# Coffee_Roaster_V2_0_Final_2025_02_24_A.net
KiCad netlist of a schematic drawn in EAGLE
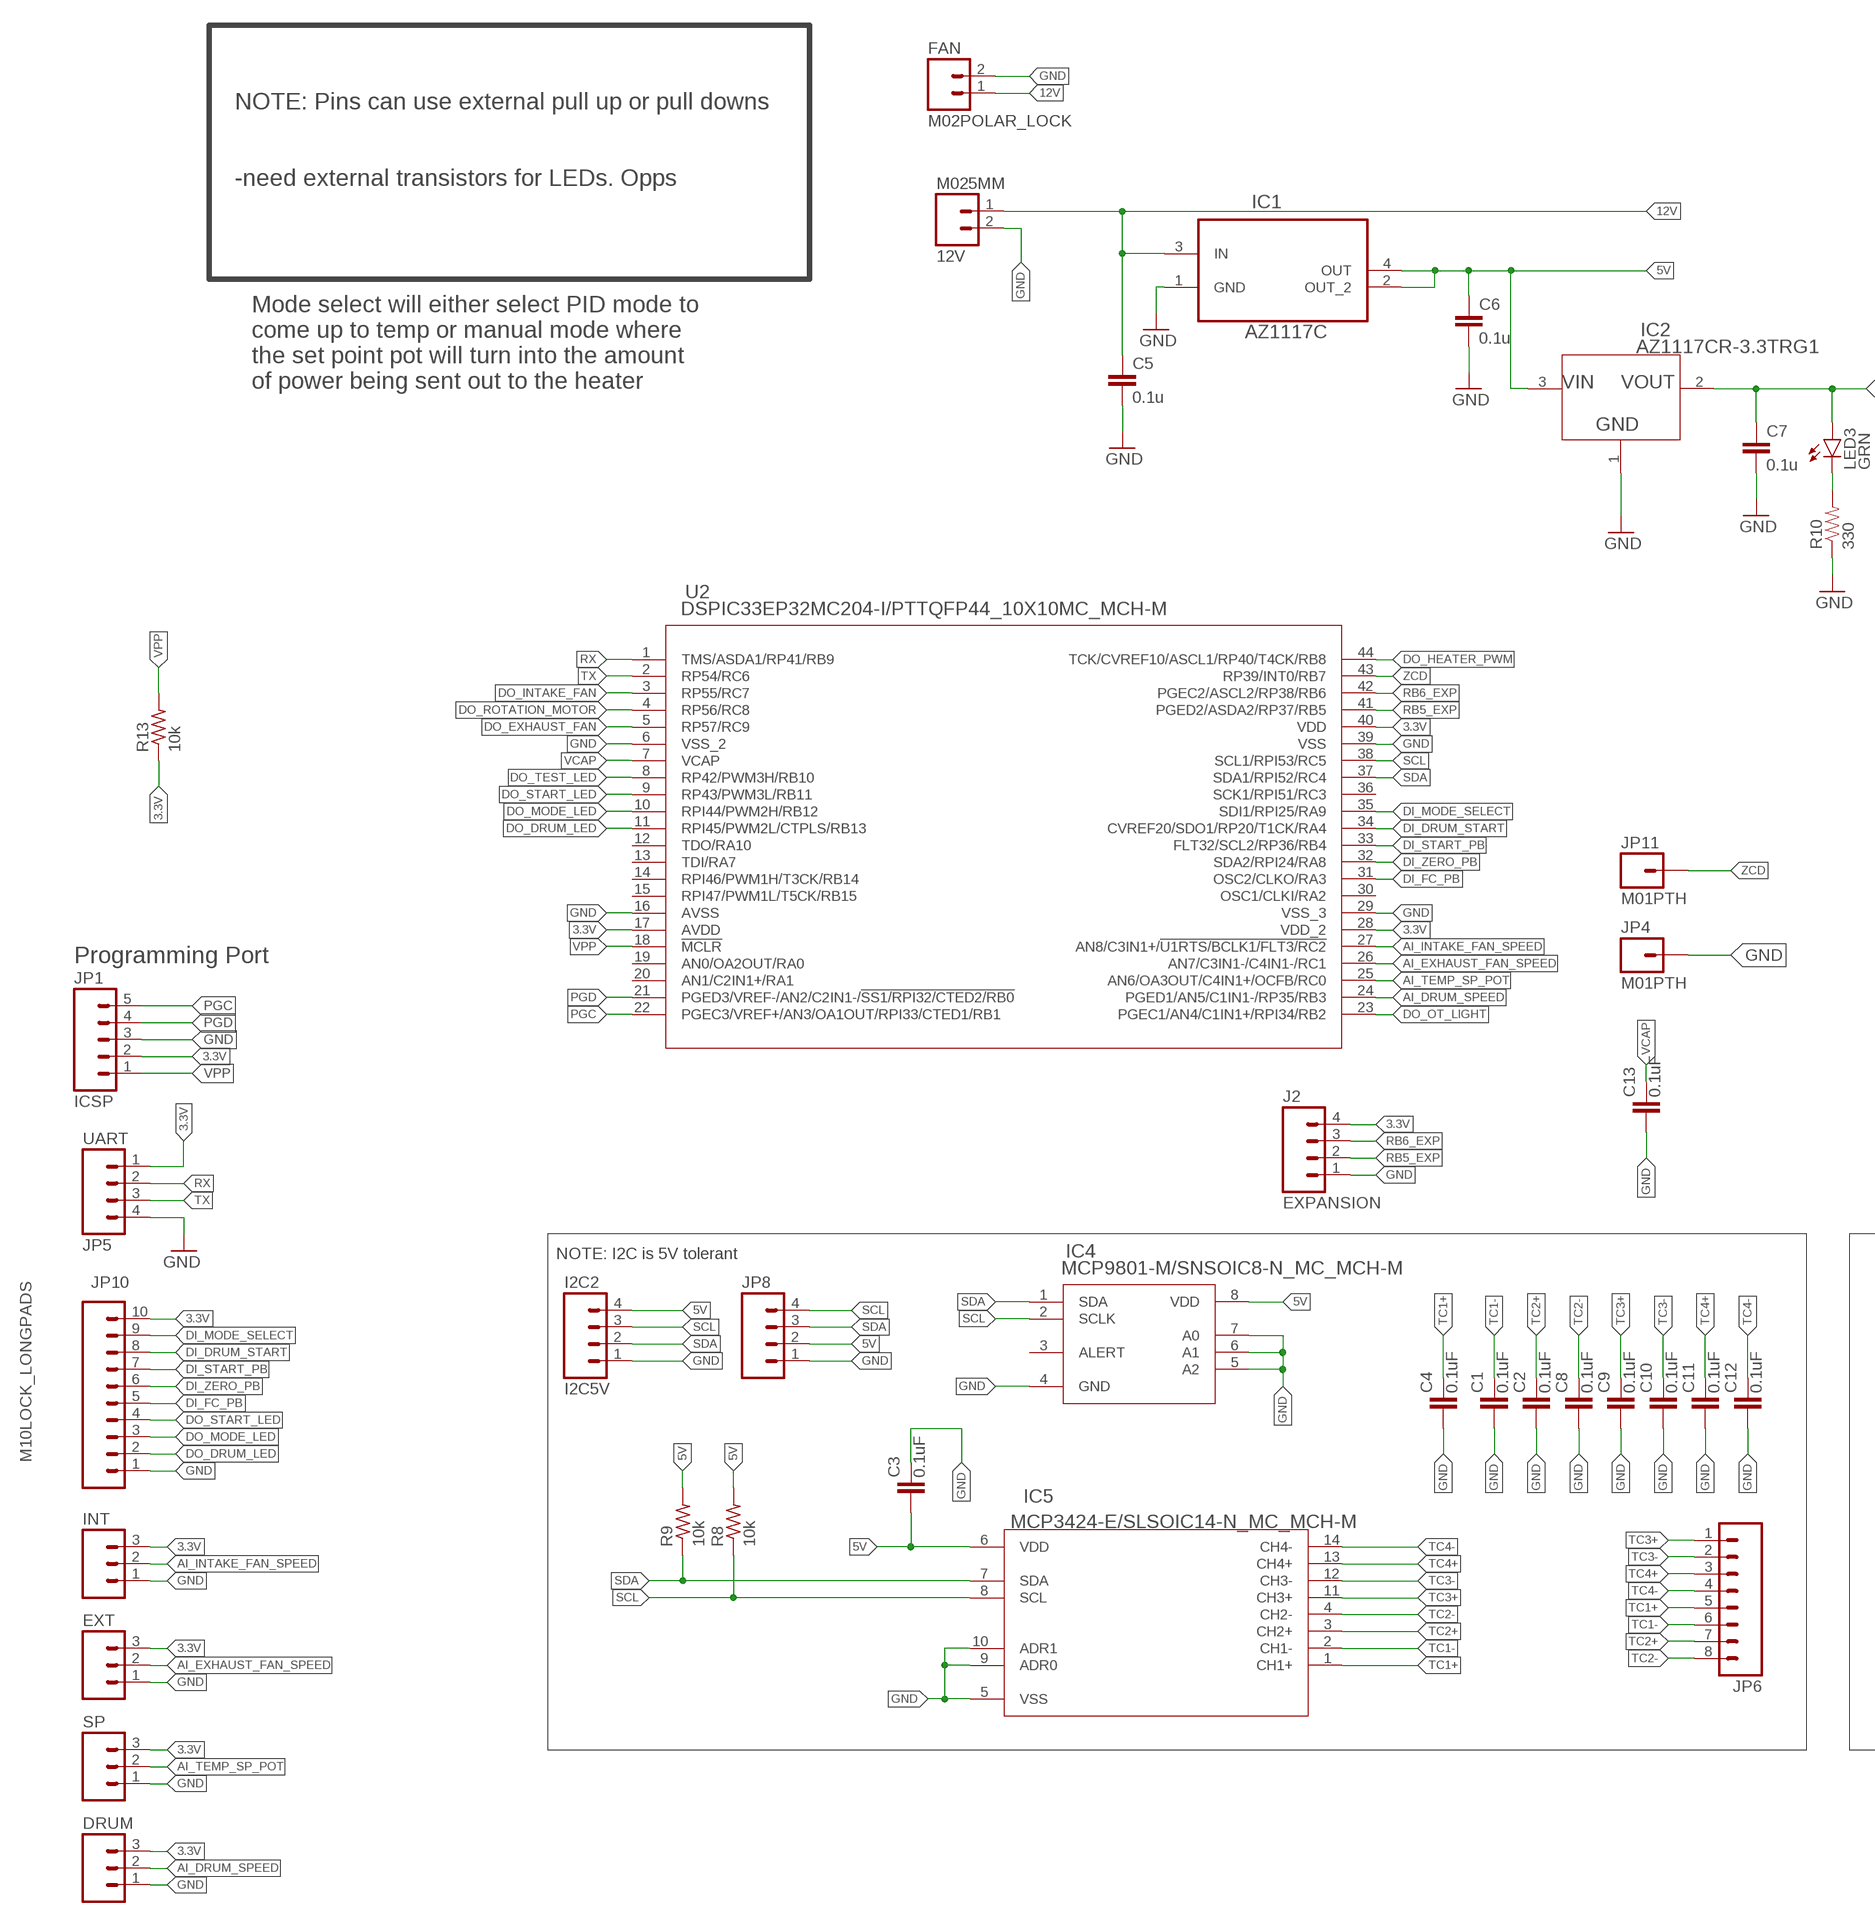
[diagram p0: schematic, sheet 1, part 1 of 2]
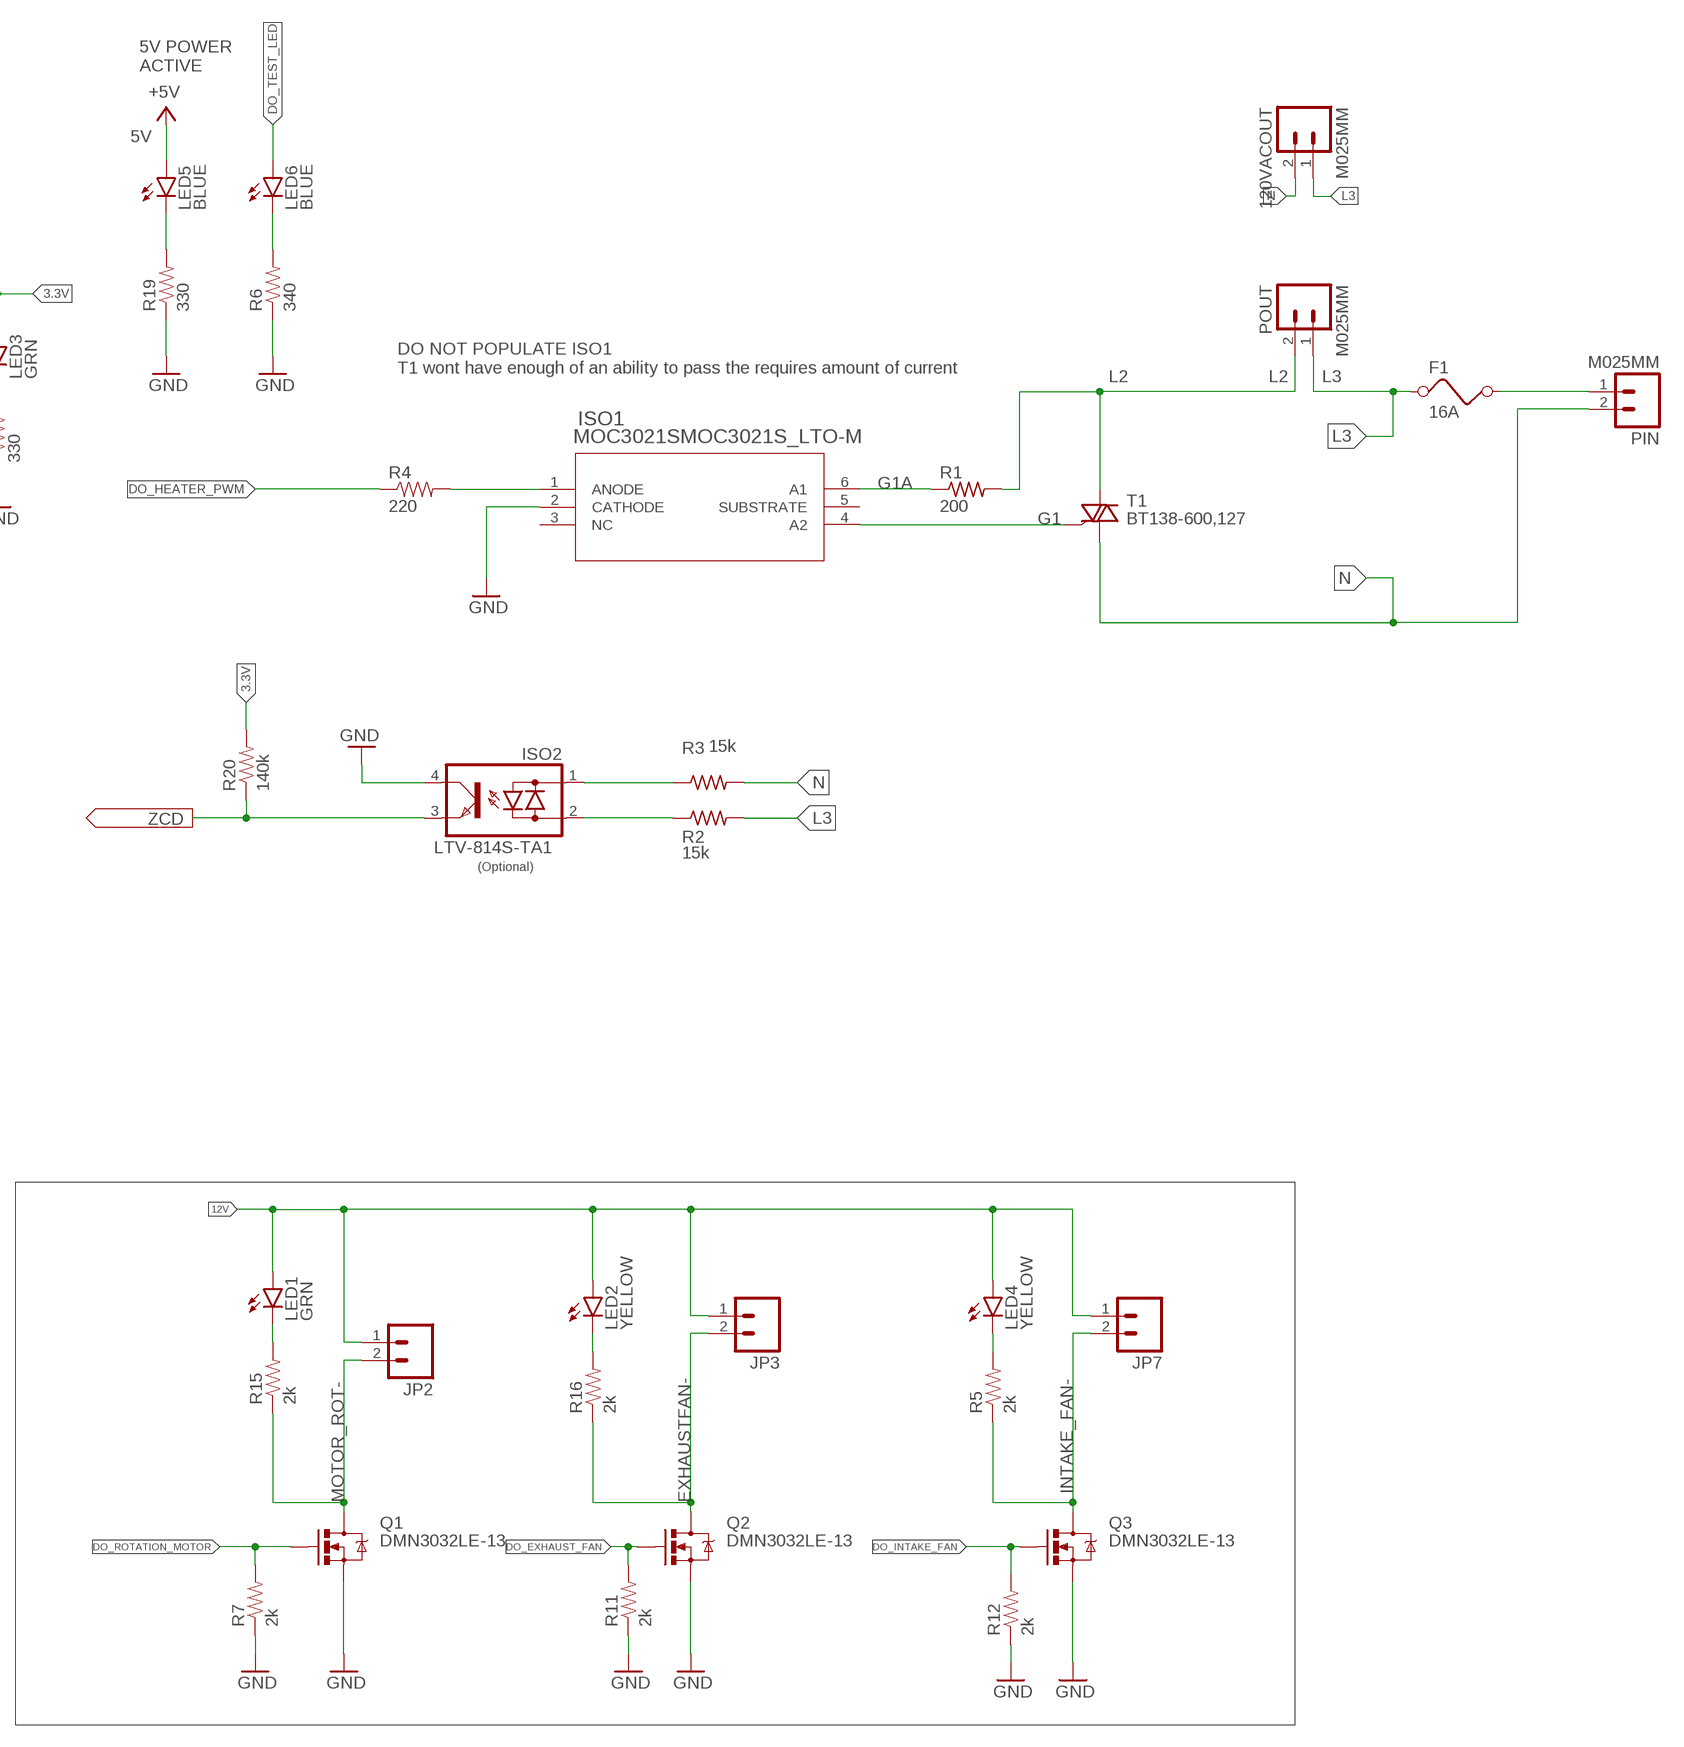
[diagram p1: schematic, sheet 1, part 2 of 2]

(export (version "E")
  (design (tool "Eeschema 10.0.6"))
  (components
    (comp (ref "12V")
      (value "M025MM")
      (footprint "eagle-import:SCREWTERMINAL-5MM-2")
      (libsource (lib "eagle-import") (part "SparkFun-Connectors_M025MM"))
    )
    (comp (ref "120VACOUT")
      (value "M025MM")
      (footprint "eagle-import:SCREWTERMINAL-5MM-2")
      (libsource (lib "eagle-import") (part "SparkFun-Connectors_M025MM"))
    )
    (comp (ref "C1")
      (value "0.1uF")
      (footprint "eagle-import:0805")
      (libsource (lib "eagle-import") (part "SparkFun-Capacitors_CAP0805"))
    )
    (comp (ref "C2")
      (value "0.1uF")
      (footprint "eagle-import:0805")
      (libsource (lib "eagle-import") (part "SparkFun-Capacitors_CAP0805"))
    )
    (comp (ref "C3")
      (value "0.1uF")
      (footprint "eagle-import:0805")
      (libsource (lib "eagle-import") (part "SparkFun-Capacitors_CAP0805"))
    )
    (comp (ref "C4")
      (value "0.1uF")
      (footprint "eagle-import:0805")
      (libsource (lib "eagle-import") (part "SparkFun-Capacitors_CAP0805"))
    )
    (comp (ref "C5")
      (value "0.1u")
      (footprint "eagle-import:1206")
      (libsource (lib "eagle-import") (part "CAP1206"))
    )
    (comp (ref "C6")
      (value "0.1u")
      (footprint "eagle-import:1206")
      (libsource (lib "eagle-import") (part "CAP1206"))
    )
    (comp (ref "C7")
      (value "0.1u")
      (footprint "eagle-import:1206")
      (libsource (lib "eagle-import") (part "CAP1206"))
    )
    (comp (ref "C8")
      (value "0.1uF")
      (footprint "eagle-import:0805")
      (libsource (lib "eagle-import") (part "SparkFun-Capacitors_CAP0805"))
    )
    (comp (ref "C9")
      (value "0.1uF")
      (footprint "eagle-import:0805")
      (libsource (lib "eagle-import") (part "SparkFun-Capacitors_CAP0805"))
    )
    (comp (ref "C10")
      (value "0.1uF")
      (footprint "eagle-import:0805")
      (libsource (lib "eagle-import") (part "SparkFun-Capacitors_CAP0805"))
    )
    (comp (ref "C11")
      (value "0.1uF")
      (footprint "eagle-import:0805")
      (libsource (lib "eagle-import") (part "SparkFun-Capacitors_CAP0805"))
    )
    (comp (ref "C12")
      (value "0.1uF")
      (footprint "eagle-import:0805")
      (libsource (lib "eagle-import") (part "SparkFun-Capacitors_CAP0805"))
    )
    (comp (ref "C13")
      (value "0.1uF")
      (footprint "eagle-import:0805")
      (libsource (lib "eagle-import") (part "SparkFun-Capacitors_CAP0805"))
    )
    (comp (ref "DRUM")
      (value "M03POLAR_LOCK")
      (footprint "eagle-import:MOLEX-1X3_LOCK")
      (libsource (lib "eagle-import") (part "M03POLAR_LOCK"))
    )
    (comp (ref "EXT")
      (value "M03POLAR_LOCK")
      (footprint "eagle-import:MOLEX-1X3_LOCK")
      (libsource (lib "eagle-import") (part "M03POLAR_LOCK"))
    )
    (comp (ref "F1")
      (value "16A")
      (footprint "eagle-import:FUSE")
      (libsource (lib "eagle-import") (part "FUSE"))
    )
    (comp (ref "FAN")
      (value "M02POLAR_LOCK")
      (footprint "eagle-import:MOLEX-1X2_LOCK")
      (libsource (lib "eagle-import") (part "SparkFun-Connectors_M02POLAR_LOCK"))
    )
    (comp (ref "I2C2")
      (value "I2C5V")
      (footprint "eagle-import:1X04-1.5MM_JST")
      (libsource (lib "eagle-import") (part "M04JST"))
    )
    (comp (ref "IC1")
      (value "AZ1117C")
      (footprint "eagle-import:SOT230P700X180-4N")
      (fields (field (name "MPN") "ADP3338AKCZ-5-R7"))
      (libsource (lib "eagle-import") (part "ADP3338AKCZ-5-R7"))
    )
    (comp (ref "IC2")
      (value "AZ1117CR-3.3TRG1")
      (footprint "eagle-import:SOT89_AZ1117_DIO")
      (fields (field (name "COPYRIGHT") "Copyright (C) 2022 Ultra Librarian. All rights reserved."))
      (libsource (lib "eagle-import") (part "AZ1117CR-3.3TRG1"))
    )
    (comp (ref "IC4")
      (value "MCP9801-M/SNSOIC8-N_MC_MCH-M")
      (footprint "eagle-import:SOIC8-N_MC_MCH-M")
      (fields
        (field (name "MANUFACTURER_PART_NUMBER") "MCP9801-M/SN")
        (field (name "COPYRIGHT") "Copyright (C) 2023 Ultra Librarian. All rights reserved.")
      )
      (libsource (lib "eagle-import") (part "MCP9801-M/SNSOIC8-N_MC_MCH-M"))
    )
    (comp (ref "IC5")
      (value "MCP3424-E/SLSOIC14-N_MC_MCH-M")
      (footprint "eagle-import:SOIC14-N_MC_MCH-M")
      (fields
        (field (name "MANUFACTURER_PART_NUMBER") "MCP3424-E/SL")
        (field (name "COPYRIGHT") "Copyright (C) 2023 Ultra Librarian. All rights reserved.")
      )
      (libsource (lib "eagle-import") (part "MCP3424-E/SLSOIC14-N_MC_MCH-M"))
    )
    (comp (ref "INT")
      (value "M03POLAR_LOCK")
      (footprint "eagle-import:MOLEX-1X3_LOCK")
      (libsource (lib "eagle-import") (part "M03POLAR_LOCK"))
    )
    (comp (ref "ISO1")
      (value "MOC3021SMOC3021S_LTO-M")
      (footprint "eagle-import:MOC3021S_LTO-M")
      (fields
        (field (name "MANUFACTURER_PART_NUMBER") "MOC3021S")
        (field (name "COPYRIGHT") "Copyright (C) 2018 Accelerated Designs. All rights reserved")
      )
      (libsource (lib "eagle-import") (part "MOC3021SMOC3021S_LTO-M"))
    )
    (comp (ref "ISO2")
      (value "LTV-814S-TA1")
      (footprint "eagle-import:DIL4-SMD")
      (fields (field (name "MF") "VISHAY/TELEFUNKEN") (field (name "MPN") "SFH6206-3"))
      (libsource (lib "eagle-import") (part "SFH6206"))
    )
    (comp (ref "J2")
      (value "EXPANSION")
      (footprint "eagle-import:1X04-1.5MM_JST")
      (libsource (lib "eagle-import") (part "M04JST"))
    )
    (comp (ref "JP1")
      (value "ICSP")
      (footprint "eagle-import:1X05")
      (libsource (lib "eagle-import") (part "M05PTH"))
    )
    (comp (ref "JP2")
      (value "M02POLAR_LOCK")
      (footprint "eagle-import:MOLEX-1X2_LOCK")
      (libsource (lib "eagle-import") (part "M02POLAR_LOCK"))
    )
    (comp (ref "JP3")
      (value "M02POLAR_LOCK")
      (footprint "eagle-import:MOLEX-1X2_LOCK")
      (libsource (lib "eagle-import") (part "M02POLAR_LOCK"))
    )
    (comp (ref "JP4")
      (value "M01PTH")
      (footprint "eagle-import:1X01")
      (libsource (lib "eagle-import") (part "M01PTH"))
    )
    (comp (ref "JP5")
      (value "UART")
      (footprint "eagle-import:1X04_LOCK")
      (libsource (lib "eagle-import") (part "M04LOCK"))
    )
    (comp (ref "JP6")
      (value "M083.5MM-8")
      (footprint "eagle-import:SCREWTERMINAL-3.5MM-8")
      (libsource (lib "eagle-import") (part "M083.5MM-8"))
    )
    (comp (ref "JP7")
      (value "M02POLAR_LOCK")
      (footprint "eagle-import:MOLEX-1X2_LOCK")
      (libsource (lib "eagle-import") (part "M02POLAR_LOCK"))
    )
    (comp (ref "JP8")
      (value "M04LOCK_LONGPADS")
      (footprint "eagle-import:1X04_LOCK_LONGPADS")
      (libsource (lib "eagle-import") (part "M04LOCK_LONGPADS"))
    )
    (comp (ref "JP10")
      (value "M10LOCK_LONGPADS")
      (footprint "eagle-import:1X10_LOCK_LONGPADS")
      (libsource (lib "eagle-import") (part "M10LOCK_LONGPADS"))
    )
    (comp (ref "JP11")
      (value "M01PTH")
      (footprint "eagle-import:1X01")
      (libsource (lib "eagle-import") (part "M01PTH"))
    )
    (comp (ref "LED1")
      (value "GRN")
      (footprint "eagle-import:LED-1206")
      (libsource (lib "eagle-import") (part "LED1206"))
    )
    (comp (ref "LED2")
      (value "YELLOW")
      (footprint "eagle-import:LED-1206")
      (libsource (lib "eagle-import") (part "LED1206"))
    )
    (comp (ref "LED3")
      (value "GRN")
      (footprint "eagle-import:LED-1206")
      (libsource (lib "eagle-import") (part "LED1206"))
    )
    (comp (ref "LED4")
      (value "YELLOW")
      (footprint "eagle-import:LED-1206")
      (libsource (lib "eagle-import") (part "LED1206"))
    )
    (comp (ref "LED5")
      (value "BLUE")
      (footprint "eagle-import:LED-1206")
      (libsource (lib "eagle-import") (part "LED1206"))
    )
    (comp (ref "LED6")
      (value "BLUE")
      (footprint "eagle-import:LED-1206")
      (libsource (lib "eagle-import") (part "LED1206"))
    )
    (comp (ref "PIN")
      (value "M025MM")
      (footprint "eagle-import:SCREWTERMINAL-5MM-2")
      (libsource (lib "eagle-import") (part "SparkFun-Connectors_M025MM"))
    )
    (comp (ref "POUT")
      (value "M025MM")
      (footprint "eagle-import:SCREWTERMINAL-5MM-2")
      (libsource (lib "eagle-import") (part "SparkFun-Connectors_M025MM"))
    )
    (comp (ref "Q1")
      (value "DMN3032LE-13")
      (footprint "eagle-import:SOT223")
      (libsource (lib "eagle-import") (part "NFET_SOT_223"))
    )
    (comp (ref "Q2")
      (value "DMN3032LE-13")
      (footprint "eagle-import:SOT223")
      (libsource (lib "eagle-import") (part "NFET_SOT_223"))
    )
    (comp (ref "Q3")
      (value "DMN3032LE-13")
      (footprint "eagle-import:SOT223")
      (libsource (lib "eagle-import") (part "NFET_SOT_223"))
    )
    (comp (ref "R1")
      (value "200")
      (footprint "eagle-import:R2512")
      (libsource (lib "eagle-import") (part "rcl_334_R-US_R2512"))
    )
    (comp (ref "R2")
      (value "15k")
      (footprint "eagle-import:R2512")
      (libsource (lib "eagle-import") (part "rcl_334_R-US_R2512"))
    )
    (comp (ref "R3")
      (value "15k")
      (footprint "eagle-import:R2512")
      (libsource (lib "eagle-import") (part "rcl_334_R-US_R2512"))
    )
    (comp (ref "R4")
      (value "220")
      (footprint "eagle-import:1206")
      (libsource (lib "eagle-import") (part "RESISTOR1206"))
    )
    (comp (ref "R5")
      (value "2k")
      (footprint "eagle-import:1206")
      (libsource (lib "eagle-import") (part "RESISTOR1206"))
    )
    (comp (ref "R6")
      (value "340")
      (footprint "eagle-import:1206")
      (libsource (lib "eagle-import") (part "RESISTOR1206"))
    )
    (comp (ref "R7")
      (value "2k")
      (footprint "eagle-import:1206")
      (libsource (lib "eagle-import") (part "RESISTOR1206"))
    )
    (comp (ref "R8")
      (value "10k")
      (footprint "eagle-import:M0805")
      (libsource (lib "eagle-import") (part "R-US_M0805"))
    )
    (comp (ref "R9")
      (value "10k")
      (footprint "eagle-import:M0805")
      (libsource (lib "eagle-import") (part "R-US_M0805"))
    )
    (comp (ref "R10")
      (value "330")
      (footprint "eagle-import:1206")
      (libsource (lib "eagle-import") (part "RESISTOR1206"))
    )
    (comp (ref "R11")
      (value "2k")
      (footprint "eagle-import:1206")
      (libsource (lib "eagle-import") (part "RESISTOR1206"))
    )
    (comp (ref "R12")
      (value "2k")
      (footprint "eagle-import:1206")
      (libsource (lib "eagle-import") (part "RESISTOR1206"))
    )
    (comp (ref "R13")
      (value "10k")
      (footprint "eagle-import:M0805")
      (libsource (lib "eagle-import") (part "R-US_M0805"))
    )
    (comp (ref "R15")
      (value "2k")
      (footprint "eagle-import:1206")
      (libsource (lib "eagle-import") (part "RESISTOR1206"))
    )
    (comp (ref "R16")
      (value "2k")
      (footprint "eagle-import:1206")
      (libsource (lib "eagle-import") (part "RESISTOR1206"))
    )
    (comp (ref "R19")
      (value "330")
      (footprint "eagle-import:1206")
      (libsource (lib "eagle-import") (part "RESISTOR1206"))
    )
    (comp (ref "R20")
      (value "140k")
      (footprint "eagle-import:1206")
      (libsource (lib "eagle-import") (part "RESISTOR1206"))
    )
    (comp (ref "SP")
      (value "M03POLAR_LOCK")
      (footprint "eagle-import:MOLEX-1X3_LOCK")
      (libsource (lib "eagle-import") (part "M03POLAR_LOCK"))
    )
    (comp (ref "T1")
      (value "BT138-600,127")
      (footprint "eagle-import:TO220BV")
      (libsource (lib "eagle-import") (part "BT138-V"))
    )
    (comp (ref "U2")
      (value "DSPIC33EP32MC204-I/PTTQFP44_10X10MC_MCH-M")
      (footprint "eagle-import:TQFP44_10X10MC_MCH-M")
      (fields
        (field (name "MANUFACTURER_PART_NUMBER") "DSPIC33EP32MC204-I/PT")
        (field (name "COPYRIGHT") "Copyright (C) 2021 Ultra Librarian. All rights reserved.")
      )
      (libsource (lib "eagle-import") (part "DSPIC33EP32MC204-I/PTTQFP44_10X10MC_MCH-M"))
    )
  )
  (nets
    (net (code "1") (name "3.3V") (class "Default")
      (node (ref "C7") (pin "1") (pinfunction "1_1") (pintype "passive"))
      (node (ref "DRUM") (pin "3") (pinfunction "3_3") (pintype "passive"))
      (node (ref "EXT") (pin "3") (pinfunction "3_3") (pintype "passive"))
      (node (ref "IC2") (pin "2") (pinfunction "OUTPUT_2") (pintype "output"))
      (node (ref "INT") (pin "3") (pinfunction "3_3") (pintype "passive"))
      (node (ref "J2") (pin "4") (pinfunction "4_4") (pintype "passive"))
      (node (ref "JP1") (pin "2") (pinfunction "2_2") (pintype "passive"))
      (node (ref "JP10") (pin "10") (pinfunction "10_10") (pintype "passive"))
      (node (ref "JP5") (pin "1") (pinfunction "1_1") (pintype "passive"))
      (node (ref "LED3") (pin "A") (pinfunction "A_A") (pintype "passive"))
      (node (ref "R13") (pin "1") (pinfunction "1_1") (pintype "passive"))
      (node (ref "R20") (pin "2") (pinfunction "2_2") (pintype "passive"))
      (node (ref "SP") (pin "3") (pinfunction "3_3") (pintype "passive"))
      (node (ref "U2") (pin "17") (pinfunction "AVDD_17") (pintype "power_in"))
      (node (ref "U2") (pin "28") (pinfunction "VDD_2_28") (pintype "power_in"))
      (node (ref "U2") (pin "40") (pinfunction "VDD_40") (pintype "power_in"))
    )
    (net (code "2") (name "5V") (class "Default")
      (node (ref "C3") (pin "1") (pinfunction "1_1") (pintype "passive"))
      (node (ref "C6") (pin "1") (pinfunction "1_1") (pintype "passive"))
      (node (ref "I2C2") (pin "4") (pinfunction "4_4") (pintype "passive"))
      (node (ref "IC1") (pin "2") (pinfunction "OUT_2_2") (pintype "output"))
      (node (ref "IC1") (pin "4") (pinfunction "OUT_4") (pintype "output"))
      (node (ref "IC2") (pin "3") (pinfunction "INPUT_3") (pintype "input"))
      (node (ref "IC4") (pin "8") (pinfunction "VDD_8") (pintype "passive"))
      (node (ref "IC5") (pin "6") (pinfunction "VDD_6") (pintype "power_in"))
      (node (ref "JP8") (pin "2") (pinfunction "2_2") (pintype "passive"))
      (node (ref "LED5") (pin "A") (pinfunction "A_A") (pintype "passive"))
      (node (ref "R8") (pin "2") (pinfunction "2_2") (pintype "passive"))
      (node (ref "R9") (pin "2") (pinfunction "2_2") (pintype "passive"))
    )
    (net (code "3") (name "12V") (class "Default")
      (node (ref "12V") (pin "1") (pinfunction "1_1") (pintype "passive"))
      (node (ref "C5") (pin "1") (pinfunction "1_1") (pintype "passive"))
      (node (ref "FAN") (pin "1") (pinfunction "1_1") (pintype "passive"))
      (node (ref "IC1") (pin "3") (pinfunction "IN_3") (pintype "input"))
      (node (ref "JP2") (pin "1") (pinfunction "1_1") (pintype "passive"))
      (node (ref "JP3") (pin "1") (pinfunction "1_1") (pintype "passive"))
      (node (ref "JP7") (pin "1") (pinfunction "1_1") (pintype "passive"))
      (node (ref "LED1") (pin "A") (pinfunction "A_A") (pintype "passive"))
      (node (ref "LED2") (pin "A") (pinfunction "A_A") (pintype "passive"))
      (node (ref "LED4") (pin "A") (pinfunction "A_A") (pintype "passive"))
    )
    (net (code "4") (name "AI_DRUM_SPEED") (class "Default")
      (node (ref "DRUM") (pin "2") (pinfunction "2_2") (pintype "passive"))
      (node (ref "U2") (pin "24") (pinfunction "PGED1/AN5/C1IN1-/RP35/RB3_24") (pintype "bidirectional"))
    )
    (net (code "5") (name "AI_EXHAUST_FAN_SPEED") (class "Default")
      (node (ref "EXT") (pin "2") (pinfunction "2_2") (pintype "passive"))
      (node (ref "U2") (pin "26") (pinfunction "AN7/C3IN1-/C4IN1-/RC1_26") (pintype "bidirectional"))
    )
    (net (code "6") (name "AI_INTAKE_FAN_SPEED") (class "Default")
      (node (ref "INT") (pin "2") (pinfunction "2_2") (pintype "passive"))
      (node (ref "U2") (pin "27") (pinfunction "AN8/C3IN1+/~{U1RTS/BCLK1/FLT3/RC2}_27") (pintype "bidirectional"))
    )
    (net (code "7") (name "AI_TEMP_SP_POT") (class "Default")
      (node (ref "SP") (pin "2") (pinfunction "2_2") (pintype "passive"))
      (node (ref "U2") (pin "25") (pinfunction "AN6/OA3OUT/C4IN1+/OCFB/RC0_25") (pintype "bidirectional"))
    )
    (net (code "8") (name "DI_DRUM_START") (class "Default")
      (node (ref "JP10") (pin "8") (pinfunction "8_8") (pintype "passive"))
      (node (ref "U2") (pin "34") (pinfunction "CVREF20/SDO1/RP20/T1CK/RA4_34") (pintype "bidirectional"))
    )
    (net (code "9") (name "DI_FC_PB") (class "Default")
      (node (ref "JP10") (pin "5") (pinfunction "5_5") (pintype "passive"))
      (node (ref "U2") (pin "31") (pinfunction "OSC2/CLKO/RA3_31") (pintype "bidirectional"))
    )
    (net (code "10") (name "DI_MODE_SELECT") (class "Default")
      (node (ref "JP10") (pin "9") (pinfunction "9_9") (pintype "passive"))
      (node (ref "U2") (pin "35") (pinfunction "SDI1/RPI25/RA9_35") (pintype "bidirectional"))
    )
    (net (code "11") (name "DI_START_PB") (class "Default")
      (node (ref "JP10") (pin "7") (pinfunction "7_7") (pintype "passive"))
      (node (ref "U2") (pin "33") (pinfunction "FLT32/SCL2/RP36/RB4_33") (pintype "bidirectional"))
    )
    (net (code "12") (name "DI_ZERO_PB") (class "Default")
      (node (ref "JP10") (pin "6") (pinfunction "6_6") (pintype "passive"))
      (node (ref "U2") (pin "32") (pinfunction "SDA2/RPI24/RA8_32") (pintype "bidirectional"))
    )
    (net (code "13") (name "DO_DRUM_LED") (class "Default")
      (node (ref "JP10") (pin "2") (pinfunction "2_2") (pintype "passive"))
      (node (ref "U2") (pin "11") (pinfunction "RPI45/PWM2L/CTPLS/RB13_11") (pintype "bidirectional"))
    )
    (net (code "14") (name "DO_EXHAUST_FAN") (class "Default")
      (node (ref "Q2") (pin "1") (pinfunction "G_1") (pintype "passive"))
      (node (ref "R11") (pin "2") (pinfunction "2_2") (pintype "passive"))
      (node (ref "U2") (pin "5") (pinfunction "RP57/RC9_5") (pintype "bidirectional"))
    )
    (net (code "15") (name "DO_HEATER_PWM") (class "Default")
      (node (ref "R4") (pin "1") (pinfunction "1_1") (pintype "passive"))
      (node (ref "U2") (pin "44") (pinfunction "TCK/CVREF10/ASCL1/RP40/T4CK/RB8_44") (pintype "bidirectional"))
    )
    (net (code "16") (name "DO_INTAKE_FAN") (class "Default")
      (node (ref "Q3") (pin "1") (pinfunction "G_1") (pintype "passive"))
      (node (ref "R12") (pin "2") (pinfunction "2_2") (pintype "passive"))
      (node (ref "U2") (pin "3") (pinfunction "RP55/RC7_3") (pintype "bidirectional"))
    )
    (net (code "17") (name "DO_MODE_LED") (class "Default")
      (node (ref "JP10") (pin "3") (pinfunction "3_3") (pintype "passive"))
      (node (ref "U2") (pin "10") (pinfunction "RPI44/PWM2H/RB12_10") (pintype "bidirectional"))
    )
    (net (code "18") (name "DO_OT_LIGHT") (class "Default")
      (node (ref "U2") (pin "23") (pinfunction "PGEC1/AN4/C1IN1+/RPI34/RB2_23") (pintype "bidirectional"))
    )
    (net (code "19") (name "DO_ROTATION_MOTOR") (class "Default")
      (node (ref "Q1") (pin "1") (pinfunction "G_1") (pintype "passive"))
      (node (ref "R7") (pin "2") (pinfunction "2_2") (pintype "passive"))
      (node (ref "U2") (pin "4") (pinfunction "RP56/RC8_4") (pintype "bidirectional"))
    )
    (net (code "20") (name "DO_START_LED") (class "Default")
      (node (ref "JP10") (pin "4") (pinfunction "4_4") (pintype "passive"))
      (node (ref "U2") (pin "9") (pinfunction "RP43/PWM3L/RB11_9") (pintype "bidirectional"))
    )
    (net (code "21") (name "DO_TEST_LED") (class "Default")
      (node (ref "LED6") (pin "A") (pinfunction "A_A") (pintype "passive"))
      (node (ref "U2") (pin "8") (pinfunction "RP42/PWM3H/RB10_8") (pintype "bidirectional"))
    )
    (net (code "22") (name "EXHAUSTFAN-") (class "Default")
      (node (ref "JP3") (pin "2") (pinfunction "2_2") (pintype "passive"))
      (node (ref "Q2") (pin "2") (pinfunction "D_2") (pintype "passive"))
      (node (ref "Q2") (pin "4") (pinfunction "D_4") (pintype "passive"))
      (node (ref "R16") (pin "1") (pinfunction "1_1") (pintype "passive"))
    )
    (net (code "23") (name "G1") (class "Default")
      (node (ref "ISO1") (pin "4") (pinfunction "A2_4") (pintype "passive"))
      (node (ref "T1") (pin "G") (pinfunction "G_G") (pintype "passive"))
    )
    (net (code "24") (name "G1A") (class "Default")
      (node (ref "ISO1") (pin "6") (pinfunction "A1_6") (pintype "passive"))
      (node (ref "R1") (pin "1") (pinfunction "1_1") (pintype "passive"))
    )
    (net (code "25") (name "GND") (class "Default")
      (node (ref "12V") (pin "2") (pinfunction "2_2") (pintype "passive"))
      (node (ref "C1") (pin "1") (pinfunction "1_1") (pintype "passive"))
      (node (ref "C10") (pin "1") (pinfunction "1_1") (pintype "passive"))
      (node (ref "C11") (pin "1") (pinfunction "1_1") (pintype "passive"))
      (node (ref "C12") (pin "1") (pinfunction "1_1") (pintype "passive"))
      (node (ref "C13") (pin "1") (pinfunction "1_1") (pintype "passive"))
      (node (ref "C2") (pin "1") (pinfunction "1_1") (pintype "passive"))
      (node (ref "C3") (pin "2") (pinfunction "2_2") (pintype "passive"))
      (node (ref "C4") (pin "1") (pinfunction "1_1") (pintype "passive"))
      (node (ref "C5") (pin "2") (pinfunction "2_2") (pintype "passive"))
      (node (ref "C6") (pin "2") (pinfunction "2_2") (pintype "passive"))
      (node (ref "C7") (pin "2") (pinfunction "2_2") (pintype "passive"))
      (node (ref "C8") (pin "1") (pinfunction "1_1") (pintype "passive"))
      (node (ref "C9") (pin "1") (pinfunction "1_1") (pintype "passive"))
      (node (ref "DRUM") (pin "1") (pinfunction "1_1") (pintype "passive"))
      (node (ref "EXT") (pin "1") (pinfunction "1_1") (pintype "passive"))
      (node (ref "FAN") (pin "2") (pinfunction "2_2") (pintype "passive"))
      (node (ref "I2C2") (pin "1") (pinfunction "1_1") (pintype "passive"))
      (node (ref "IC1") (pin "1") (pinfunction "GND_1") (pintype "passive"))
      (node (ref "IC2") (pin "1") (pinfunction "ADJ/GND_1") (pintype "passive"))
      (node (ref "IC4") (pin "4") (pinfunction "GND_4") (pintype "passive"))
      (node (ref "IC4") (pin "5") (pinfunction "A2_5") (pintype "passive"))
      (node (ref "IC4") (pin "6") (pinfunction "A1_6") (pintype "passive"))
      (node (ref "IC4") (pin "7") (pinfunction "A0_7") (pintype "passive"))
      (node (ref "IC5") (pin "10") (pinfunction "ADR1_10") (pintype "passive"))
      (node (ref "IC5") (pin "5") (pinfunction "VSS_5") (pintype "power_in"))
      (node (ref "IC5") (pin "9") (pinfunction "ADR0_9") (pintype "passive"))
      (node (ref "INT") (pin "1") (pinfunction "1_1") (pintype "passive"))
      (node (ref "ISO1") (pin "2") (pinfunction "CATHODE_2") (pintype "passive"))
      (node (ref "ISO2") (pin "4") (pinfunction "C_4") (pintype "passive"))
      (node (ref "J2") (pin "1") (pinfunction "1_1") (pintype "passive"))
      (node (ref "JP1") (pin "3") (pinfunction "3_3") (pintype "passive"))
      (node (ref "JP10") (pin "1") (pinfunction "1_1") (pintype "passive"))
      (node (ref "JP4") (pin "1") (pinfunction "1_1") (pintype "passive"))
      (node (ref "JP5") (pin "4") (pinfunction "4_4") (pintype "passive"))
      (node (ref "JP8") (pin "1") (pinfunction "1_1") (pintype "passive"))
      (node (ref "Q1") (pin "3") (pinfunction "S_3") (pintype "passive"))
      (node (ref "Q2") (pin "3") (pinfunction "S_3") (pintype "passive"))
      (node (ref "Q3") (pin "3") (pinfunction "S_3") (pintype "passive"))
      (node (ref "R10") (pin "1") (pinfunction "1_1") (pintype "passive"))
      (node (ref "R11") (pin "1") (pinfunction "1_1") (pintype "passive"))
      (node (ref "R12") (pin "1") (pinfunction "1_1") (pintype "passive"))
      (node (ref "R19") (pin "1") (pinfunction "1_1") (pintype "passive"))
      (node (ref "R6") (pin "1") (pinfunction "1_1") (pintype "passive"))
      (node (ref "R7") (pin "1") (pinfunction "1_1") (pintype "passive"))
      (node (ref "SP") (pin "1") (pinfunction "1_1") (pintype "passive"))
      (node (ref "U2") (pin "16") (pinfunction "AVSS_16") (pintype "power_in"))
      (node (ref "U2") (pin "29") (pinfunction "VSS_3_29") (pintype "power_in"))
      (node (ref "U2") (pin "39") (pinfunction "VSS_39") (pintype "power_in"))
      (node (ref "U2") (pin "6") (pinfunction "VSS_2_6") (pintype "power_in"))
    )
    (net (code "26") (name "INTAKE_FAN-") (class "Default")
      (node (ref "JP7") (pin "2") (pinfunction "2_2") (pintype "passive"))
      (node (ref "Q3") (pin "2") (pinfunction "D_2") (pintype "passive"))
      (node (ref "Q3") (pin "4") (pinfunction "D_4") (pintype "passive"))
      (node (ref "R5") (pin "1") (pinfunction "1_1") (pintype "passive"))
    )
    (net (code "27") (name "L2") (class "Default")
      (node (ref "POUT") (pin "2") (pinfunction "2_2") (pintype "passive"))
      (node (ref "R1") (pin "2") (pinfunction "2_2") (pintype "passive"))
      (node (ref "T1") (pin "T2") (pinfunction "A2_T2") (pintype "passive"))
    )
    (net (code "28") (name "L3") (class "Default")
      (node (ref "120VACOUT") (pin "1") (pinfunction "1_1") (pintype "passive"))
      (node (ref "F1") (pin "1") (pinfunction "1_1") (pintype "passive"))
      (node (ref "POUT") (pin "1") (pinfunction "1_1") (pintype "passive"))
      (node (ref "R2") (pin "2") (pinfunction "2_2") (pintype "passive"))
    )
    (net (code "29") (name "MOTOR_ROT-") (class "Default")
      (node (ref "JP2") (pin "2") (pinfunction "2_2") (pintype "passive"))
      (node (ref "Q1") (pin "2") (pinfunction "D_2") (pintype "passive"))
      (node (ref "Q1") (pin "4") (pinfunction "D_4") (pintype "passive"))
      (node (ref "R15") (pin "1") (pinfunction "1_1") (pintype "passive"))
    )
    (net (code "30") (name "N") (class "Default")
      (node (ref "120VACOUT") (pin "2") (pinfunction "2_2") (pintype "passive"))
      (node (ref "PIN") (pin "2") (pinfunction "2_2") (pintype "passive"))
      (node (ref "R3") (pin "2") (pinfunction "2_2") (pintype "passive"))
      (node (ref "T1") (pin "T1") (pinfunction "A1_T1") (pintype "passive"))
    )
    (net (code "31") (name "Net-(F1-Pad2)") (class "Default")
      (node (ref "F1") (pin "2") (pinfunction "2_2") (pintype "passive"))
      (node (ref "PIN") (pin "1") (pinfunction "1_1") (pintype "passive"))
    )
    (net (code "32") (name "Net-(ISO1-ANODE)") (class "Default")
      (node (ref "ISO1") (pin "1") (pinfunction "ANODE_1") (pintype "passive"))
      (node (ref "R4") (pin "2") (pinfunction "2_2") (pintype "passive"))
    )
    (net (code "33") (name "Net-(ISO2-AC1)") (class "Default")
      (node (ref "ISO2") (pin "1") (pinfunction "AC1_1") (pintype "passive"))
      (node (ref "R3") (pin "1") (pinfunction "1_1") (pintype "passive"))
    )
    (net (code "34") (name "Net-(ISO2-AC2)") (class "Default")
      (node (ref "ISO2") (pin "2") (pinfunction "AC2_2") (pintype "passive"))
      (node (ref "R2") (pin "1") (pinfunction "1_1") (pintype "passive"))
    )
    (net (code "35") (name "Net-(LED1-PadC)") (class "Default")
      (node (ref "LED1") (pin "C") (pinfunction "C_C") (pintype "passive"))
      (node (ref "R15") (pin "2") (pinfunction "2_2") (pintype "passive"))
    )
    (net (code "36") (name "Net-(LED2-PadC)") (class "Default")
      (node (ref "LED2") (pin "C") (pinfunction "C_C") (pintype "passive"))
      (node (ref "R16") (pin "2") (pinfunction "2_2") (pintype "passive"))
    )
    (net (code "37") (name "Net-(LED3-PadC)") (class "Default")
      (node (ref "LED3") (pin "C") (pinfunction "C_C") (pintype "passive"))
      (node (ref "R10") (pin "2") (pinfunction "2_2") (pintype "passive"))
    )
    (net (code "38") (name "Net-(LED4-PadC)") (class "Default")
      (node (ref "LED4") (pin "C") (pinfunction "C_C") (pintype "passive"))
      (node (ref "R5") (pin "2") (pinfunction "2_2") (pintype "passive"))
    )
    (net (code "39") (name "Net-(LED5-PadC)") (class "Default")
      (node (ref "LED5") (pin "C") (pinfunction "C_C") (pintype "passive"))
      (node (ref "R19") (pin "2") (pinfunction "2_2") (pintype "passive"))
    )
    (net (code "40") (name "Net-(LED6-PadC)") (class "Default")
      (node (ref "LED6") (pin "C") (pinfunction "C_C") (pintype "passive"))
      (node (ref "R6") (pin "2") (pinfunction "2_2") (pintype "passive"))
    )
    (net (code "41") (name "PGC") (class "Default")
      (node (ref "JP1") (pin "5") (pinfunction "5_5") (pintype "passive"))
      (node (ref "U2") (pin "22") (pinfunction "PGEC3/VREF+/AN3/OA1OUT/RPI33/CTED1/RB1_22") (pintype "bidirectional"))
    )
    (net (code "42") (name "PGD") (class "Default")
      (node (ref "JP1") (pin "4") (pinfunction "4_4") (pintype "passive"))
      (node (ref "U2") (pin "21") (pinfunction "PGED3/VREF-/AN2/C2IN1-/~{SS1/RPI32/CTED2/RB0}_21") (pintype "bidirectional"))
    )
    (net (code "43") (name "RB5_EXP") (class "Default")
      (node (ref "J2") (pin "2") (pinfunction "2_2") (pintype "passive"))
      (node (ref "U2") (pin "41") (pinfunction "PGED2/ASDA2/RP37/RB5_41") (pintype "bidirectional"))
    )
    (net (code "44") (name "RB6_EXP") (class "Default")
      (node (ref "J2") (pin "3") (pinfunction "3_3") (pintype "passive"))
      (node (ref "U2") (pin "42") (pinfunction "PGEC2/ASCL2/RP38/RB6_42") (pintype "bidirectional"))
    )
    (net (code "45") (name "RX") (class "Default")
      (node (ref "JP5") (pin "2") (pinfunction "2_2") (pintype "passive"))
      (node (ref "U2") (pin "1") (pinfunction "TMS/ASDA1/RP41/RB9_1") (pintype "bidirectional"))
    )
    (net (code "46") (name "SCL") (class "Default")
      (node (ref "I2C2") (pin "3") (pinfunction "3_3") (pintype "passive"))
      (node (ref "IC4") (pin "2") (pinfunction "SCLK_2") (pintype "passive"))
      (node (ref "IC5") (pin "8") (pinfunction "SCL_8") (pintype "input"))
      (node (ref "JP8") (pin "4") (pinfunction "4_4") (pintype "passive"))
      (node (ref "R8") (pin "1") (pinfunction "1_1") (pintype "passive"))
      (node (ref "U2") (pin "38") (pinfunction "SCL1/RPI53/RC5_38") (pintype "bidirectional"))
    )
    (net (code "47") (name "SDA") (class "Default")
      (node (ref "I2C2") (pin "2") (pinfunction "2_2") (pintype "passive"))
      (node (ref "IC4") (pin "1") (pinfunction "SDA_1") (pintype "passive"))
      (node (ref "IC5") (pin "7") (pinfunction "SDA_7") (pintype "bidirectional"))
      (node (ref "JP8") (pin "3") (pinfunction "3_3") (pintype "passive"))
      (node (ref "R9") (pin "1") (pinfunction "1_1") (pintype "passive"))
      (node (ref "U2") (pin "37") (pinfunction "SDA1/RPI52/RC4_37") (pintype "bidirectional"))
    )
    (net (code "48") (name "TC1+") (class "Default")
      (node (ref "C4") (pin "2") (pinfunction "2_2") (pintype "passive"))
      (node (ref "IC5") (pin "1") (pinfunction "CH1+_1") (pintype "input"))
      (node (ref "JP6") (pin "5") (pinfunction "5_5") (pintype "passive"))
    )
    (net (code "49") (name "TC1-") (class "Default")
      (node (ref "C1") (pin "2") (pinfunction "2_2") (pintype "passive"))
      (node (ref "IC5") (pin "2") (pinfunction "CH1-_2") (pintype "input"))
      (node (ref "JP6") (pin "6") (pinfunction "6_6") (pintype "passive"))
    )
    (net (code "50") (name "TC2+") (class "Default")
      (node (ref "C2") (pin "2") (pinfunction "2_2") (pintype "passive"))
      (node (ref "IC5") (pin "3") (pinfunction "CH2+_3") (pintype "input"))
      (node (ref "JP6") (pin "7") (pinfunction "7_7") (pintype "passive"))
    )
    (net (code "51") (name "TC2-") (class "Default")
      (node (ref "C8") (pin "2") (pinfunction "2_2") (pintype "passive"))
      (node (ref "IC5") (pin "4") (pinfunction "CH2-_4") (pintype "input"))
      (node (ref "JP6") (pin "8") (pinfunction "8_8") (pintype "passive"))
    )
    (net (code "52") (name "TC3+") (class "Default")
      (node (ref "C9") (pin "2") (pinfunction "2_2") (pintype "passive"))
      (node (ref "IC5") (pin "11") (pinfunction "CH3+_11") (pintype "input"))
      (node (ref "JP6") (pin "1") (pinfunction "1_1") (pintype "passive"))
    )
    (net (code "53") (name "TC3-") (class "Default")
      (node (ref "C10") (pin "2") (pinfunction "2_2") (pintype "passive"))
      (node (ref "IC5") (pin "12") (pinfunction "CH3-_12") (pintype "input"))
      (node (ref "JP6") (pin "2") (pinfunction "2_2") (pintype "passive"))
    )
    (net (code "54") (name "TC4+") (class "Default")
      (node (ref "C11") (pin "2") (pinfunction "2_2") (pintype "passive"))
      (node (ref "IC5") (pin "13") (pinfunction "CH4+_13") (pintype "input"))
      (node (ref "JP6") (pin "3") (pinfunction "3_3") (pintype "passive"))
    )
    (net (code "55") (name "TC4-") (class "Default")
      (node (ref "C12") (pin "2") (pinfunction "2_2") (pintype "passive"))
      (node (ref "IC5") (pin "14") (pinfunction "CH4-_14") (pintype "input"))
      (node (ref "JP6") (pin "4") (pinfunction "4_4") (pintype "passive"))
    )
    (net (code "56") (name "TX") (class "Default")
      (node (ref "JP5") (pin "3") (pinfunction "3_3") (pintype "passive"))
      (node (ref "U2") (pin "2") (pinfunction "RP54/RC6_2") (pintype "bidirectional"))
    )
    (net (code "57") (name "VCAP") (class "Default")
      (node (ref "C13") (pin "2") (pinfunction "2_2") (pintype "passive"))
      (node (ref "U2") (pin "7") (pinfunction "VCAP_7") (pintype "power_in"))
    )
    (net (code "58") (name "VPP") (class "Default")
      (node (ref "JP1") (pin "1") (pinfunction "1_1") (pintype "passive"))
      (node (ref "R13") (pin "2") (pinfunction "2_2") (pintype "passive"))
      (node (ref "U2") (pin "18") (pinfunction "~{MCLR}_18") (pintype "bidirectional"))
    )
    (net (code "59") (name "ZCD") (class "Default")
      (node (ref "ISO2") (pin "3") (pinfunction "E_3") (pintype "passive"))
      (node (ref "JP11") (pin "1") (pinfunction "1_1") (pintype "passive"))
      (node (ref "R20") (pin "1") (pinfunction "1_1") (pintype "passive"))
      (node (ref "U2") (pin "43") (pinfunction "RP39/INT0/RB7_43") (pintype "bidirectional"))
    )
    (net (code "60") (name "unconnected-(IC4-ALERT-Pad3)") (class "Default")
      (node (ref "IC4") (pin "3") (pinfunction "ALERT_3") (pintype "passive"))
    )
    (net (code "61") (name "unconnected-(ISO1-NC-Pad3)") (class "Default")
      (node (ref "ISO1") (pin "3") (pinfunction "NC_3") (pintype "passive"))
    )
    (net (code "62") (name "unconnected-(ISO1-SUBSTRATE-Pad5)") (class "Default")
      (node (ref "ISO1") (pin "5") (pinfunction "SUBSTRATE_5") (pintype "passive"))
    )
    (net (code "63") (name "unconnected-(U2-AN0{slash}OA2OUT{slash}RA0-Pad19)") (class "Default")
      (node (ref "U2") (pin "19") (pinfunction "AN0/OA2OUT/RA0_19") (pintype "bidirectional"))
    )
    (net (code "64") (name "unconnected-(U2-AN1{slash}C2IN1+{slash}RA1-Pad20)") (class "Default")
      (node (ref "U2") (pin "20") (pinfunction "AN1/C2IN1+/RA1_20") (pintype "bidirectional"))
    )
    (net (code "65") (name "unconnected-(U2-OSC1{slash}CLKI{slash}RA2-Pad30)") (class "Default")
      (node (ref "U2") (pin "30") (pinfunction "OSC1/CLKI/RA2_30") (pintype "bidirectional"))
    )
    (net (code "66") (name "unconnected-(U2-RPI46{slash}PWM1H{slash}T3CK{slash}RB14-Pad14)") (class "Default")
      (node (ref "U2") (pin "14") (pinfunction "RPI46/PWM1H/T3CK/RB14_14") (pintype "bidirectional"))
    )
    (net (code "67") (name "unconnected-(U2-RPI47{slash}PWM1L{slash}T5CK{slash}RB15-Pad15)") (class "Default")
      (node (ref "U2") (pin "15") (pinfunction "RPI47/PWM1L/T5CK/RB15_15") (pintype "bidirectional"))
    )
    (net (code "68") (name "unconnected-(U2-SCK1{slash}RPI51{slash}RC3-Pad36)") (class "Default")
      (node (ref "U2") (pin "36") (pinfunction "SCK1/RPI51/RC3_36") (pintype "bidirectional"))
    )
    (net (code "69") (name "unconnected-(U2-TDI{slash}RA7-Pad13)") (class "Default")
      (node (ref "U2") (pin "13") (pinfunction "TDI/RA7_13") (pintype "bidirectional"))
    )
    (net (code "70") (name "unconnected-(U2-TDO{slash}RA10-Pad12)") (class "Default")
      (node (ref "U2") (pin "12") (pinfunction "TDO/RA10_12") (pintype "bidirectional"))
    )
  )
)
